# PIR_Circuit.net
KiCad netlist of a schematic drawn in EAGLE
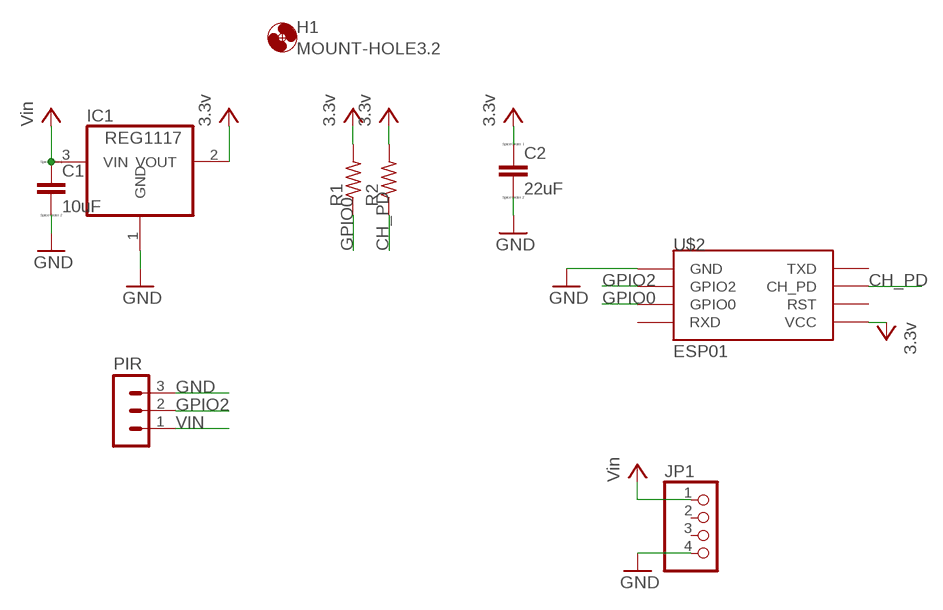
[diagram p0: schematic, sheet 1]

(export (version "E")
  (design (tool "Eeschema 10.0.6"))
  (components
    (comp (ref "C1")
      (value "10uF")
      (footprint "eagle-import:C0805")
      (libsource (lib "eagle-import") (part "C"))
    )
    (comp (ref "C2")
      (value "22uF")
      (footprint "eagle-import:C0805")
      (libsource (lib "eagle-import") (part "C"))
    )
    (comp (ref "H1")
      (value "MOUNT-HOLE3.2")
      (footprint "eagle-import:3,2")
      (libsource (lib "eagle-import") (part "MOUNT-HOLE3.2"))
    )
    (comp (ref "IC1")
      (value "REG1117")
      (footprint "eagle-import:SOT223")
      (libsource (lib "eagle-import") (part "REG1117"))
    )
    (comp (ref "JP1")
      (value "PINHD-1X4/90")
      (footprint "eagle-import:1X04_90")
      (libsource (lib "eagle-import") (part "PINHD-1X4/90"))
    )
    (comp (ref "PIR")
      (value "MA03-1")
      (footprint "eagle-import:MA03-1")
      (libsource (lib "eagle-import") (part "MA03-1"))
    )
    (comp (ref "R1")
      (value "R-US_M1206")
      (footprint "eagle-import:M1206")
      (libsource (lib "eagle-import") (part "R-US_M1206"))
    )
    (comp (ref "R2")
      (value "R-US_M1206")
      (footprint "eagle-import:M1206")
      (libsource (lib "eagle-import") (part "R-US_M1206"))
    )
    (comp (ref "U$2")
      (value "ESP01")
      (footprint "eagle-import:ESP01")
      (libsource (lib "eagle-import") (part "ESP01"))
    )
  )
  (nets
    (net (code "1") (name "/CH_PD") (class "Default")
      (node (ref "R2") (pin "1") (pinfunction "1_1") (pintype "passive"))
      (node (ref "U$2") (pin "CH_PD") (pinfunction "CH_PD_CH_PD") (pintype "bidirectional"))
    )
    (net (code "2") (name "/GPIO0") (class "Default")
      (node (ref "R1") (pin "1") (pinfunction "1_1") (pintype "passive"))
      (node (ref "U$2") (pin "GPIO0") (pinfunction "GPIO0_GPIO0") (pintype "bidirectional"))
    )
    (net (code "3") (name "/GPIO2") (class "Default")
      (node (ref "PIR") (pin "2") (pinfunction "2_2") (pintype "passive"))
      (node (ref "U$2") (pin "GPIO2") (pinfunction "GPIO2_GPIO2") (pintype "bidirectional"))
    )
    (net (code "4") (name "3.3v") (class "Default")
      (node (ref "C2") (pin "1") (pinfunction "1_1") (pintype "passive"))
      (node (ref "IC1") (pin "2") (pinfunction "VOUT_2") (pintype "output"))
      (node (ref "R1") (pin "2") (pinfunction "2_2") (pintype "passive"))
      (node (ref "R2") (pin "2") (pinfunction "2_2") (pintype "passive"))
      (node (ref "U$2") (pin "VCC") (pinfunction "VCC_VCC") (pintype "bidirectional"))
    )
    (net (code "5") (name "GND") (class "Default")
      (node (ref "C1") (pin "2") (pinfunction "2_2") (pintype "passive"))
      (node (ref "C2") (pin "2") (pinfunction "2_2") (pintype "passive"))
      (node (ref "IC1") (pin "1") (pinfunction "GND_1") (pintype "power_in"))
      (node (ref "JP1") (pin "4") (pinfunction "4_4") (pintype "passive"))
      (node (ref "PIR") (pin "3") (pinfunction "3_3") (pintype "passive"))
      (node (ref "U$2") (pin "GND") (pinfunction "GND_GND") (pintype "bidirectional"))
    )
    (net (code "6") (name "Vin") (class "Default")
      (node (ref "C1") (pin "1") (pinfunction "1_1") (pintype "passive"))
      (node (ref "IC1") (pin "3") (pinfunction "VIN_3") (pintype "input"))
      (node (ref "JP1") (pin "1") (pinfunction "1_1") (pintype "passive"))
      (node (ref "PIR") (pin "1") (pinfunction "1_1") (pintype "passive"))
    )
    (net (code "7") (name "unconnected-(JP1-Pad2)") (class "Default")
      (node (ref "JP1") (pin "2") (pinfunction "2_2") (pintype "passive"))
    )
    (net (code "8") (name "unconnected-(JP1-Pad3)") (class "Default")
      (node (ref "JP1") (pin "3") (pinfunction "3_3") (pintype "passive"))
    )
    (net (code "9") (name "unconnected-(U$2-PadRST)") (class "Default")
      (node (ref "U$2") (pin "RST") (pinfunction "RST_RST") (pintype "bidirectional"))
    )
    (net (code "10") (name "unconnected-(U$2-RXD-PadRX)") (class "Default")
      (node (ref "U$2") (pin "RX") (pinfunction "RXD_RX") (pintype "bidirectional"))
    )
    (net (code "11") (name "unconnected-(U$2-TXD-PadTX)") (class "Default")
      (node (ref "U$2") (pin "TX") (pinfunction "TXD_TX") (pintype "bidirectional"))
    )
  )
)
